# ProPrj_cdweather_2025-08-09.net
KiCad netlist of a schematic drawn in EasyEDA Pro
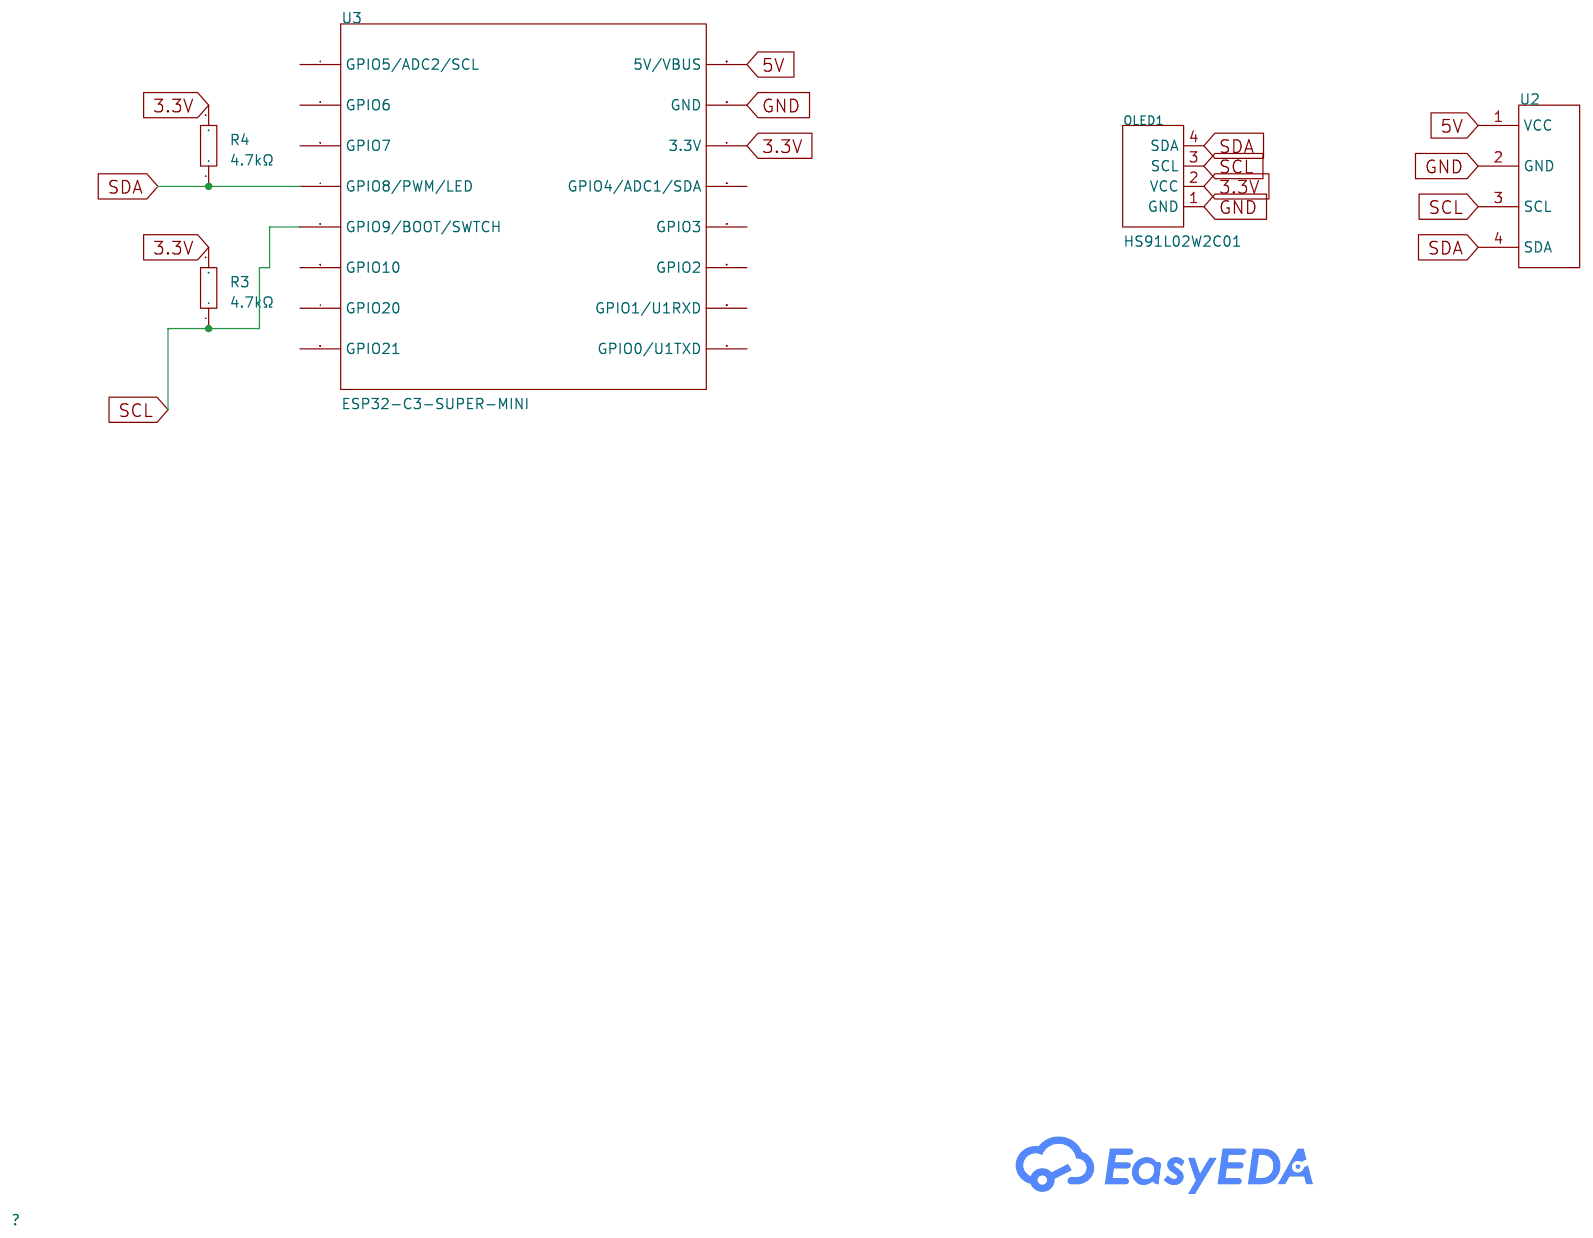
[diagram p0: schematic sheet]

(export (version "E")
  (design (tool "Eeschema 10.0.6"))
  (components
    (comp (ref "OLED1")
      (value "HS91L02W2C01")
      (footprint "easyedapro:OLED-TH_L38.0-W12.0_HS91L02W2C01")
      (fields (field (name "Manufacturer") "HS(汉昇)"))
      (libsource (lib "easyedapro") (part "HS91L02W2C01"))
    )
    (comp (ref "R3")
      (value "4.7kΩ")
      (footprint "easyedapro:RES-TH_BD2.3-L6.5-P10.50-D0.5")
      (fields
        (field (name "Manufacturer Part") "CF1/4W-4.7KΩ±5% T")
        (field (name "Manufacturer") "CCO(千志电子)")
      )
      (libsource (lib "easyedapro") (part "CF1/4W-4.7KΩ±5% T52"))
    )
    (comp (ref "R4")
      (value "4.7kΩ")
      (footprint "easyedapro:RES-TH_BD2.3-L6.5-P10.50-D0.5")
      (fields
        (field (name "Manufacturer Part") "CF1/4W-4.7KΩ±5% T")
        (field (name "Manufacturer") "CCO(千志电子)")
      )
      (libsource (lib "easyedapro") (part "CF1/4W-4.7KΩ±5% T52"))
    )
    (comp (ref "U2")
      (value "~")
      (footprint "easyedapro:BME280 Module - V")
      (libsource (lib "easyedapro") (part "BME280 Module - V"))
    )
    (comp (ref "U3")
      (value "ESP32-C3-SUPER-MINI")
      (fields (field (name "Manufacturer") "Maker go"))
      (libsource (lib "easyedapro") (part "ESP32-C3-SUPER-MINI"))
    )
  )
  (nets
    (net (code "1") (name "3.3V") (class "Default")
      (node (ref "OLED1") (pin "2") (pinfunction "VCC_2") (pintype "input"))
      (node (ref "R3") (pin "2") (pinfunction "2_2") (pintype "unspecified"))
      (node (ref "R4") (pin "2") (pinfunction "2_2") (pintype "unspecified"))
      (node (ref "U3") (pin "14") (pinfunction "3.3V_14") (pintype "unspecified"))
    )
    (net (code "2") (name "5V") (class "Default")
      (node (ref "U2") (pin "1") (pinfunction "VCC_1") (pintype "input"))
      (node (ref "U3") (pin "16") (pinfunction "5V/VBUS_16") (pintype "unspecified"))
    )
    (net (code "3") (name "GND") (class "Default")
      (node (ref "OLED1") (pin "1") (pinfunction "GND_1") (pintype "input"))
      (node (ref "U2") (pin "2") (pinfunction "GND_2") (pintype "input"))
      (node (ref "U3") (pin "15") (pinfunction "GND_15") (pintype "unspecified"))
    )
    (net (code "4") (name "SCL") (class "Default")
      (node (ref "OLED1") (pin "3") (pinfunction "SCL_3") (pintype "input"))
      (node (ref "R3") (pin "1") (pinfunction "1_1") (pintype "unspecified"))
      (node (ref "U2") (pin "3") (pinfunction "SCL_3") (pintype "input"))
      (node (ref "U3") (pin "5") (pinfunction "GPIO9/BOOT/SWTCH_5") (pintype "unspecified"))
    )
    (net (code "5") (name "SDA") (class "Default")
      (node (ref "OLED1") (pin "4") (pinfunction "SDA_4") (pintype "input"))
      (node (ref "R4") (pin "1") (pinfunction "1_1") (pintype "unspecified"))
      (node (ref "U2") (pin "4") (pinfunction "SDA_4") (pintype "input"))
      (node (ref "U3") (pin "4") (pinfunction "GPIO8/PWM/LED_4") (pintype "unspecified"))
    )
    (net (code "6") (name "unconnected-(U3-GPIO0{slash}U1TXD-Pad9)") (class "Default")
      (node (ref "U3") (pin "9") (pinfunction "GPIO0/U1TXD_9") (pintype "unspecified"))
    )
    (net (code "7") (name "unconnected-(U3-GPIO1{slash}U1RXD-Pad10)") (class "Default")
      (node (ref "U3") (pin "10") (pinfunction "GPIO1/U1RXD_10") (pintype "unspecified"))
    )
    (net (code "8") (name "unconnected-(U3-GPIO2-Pad11)") (class "Default")
      (node (ref "U3") (pin "11") (pinfunction "GPIO2_11") (pintype "unspecified"))
    )
    (net (code "9") (name "unconnected-(U3-GPIO3-Pad12)") (class "Default")
      (node (ref "U3") (pin "12") (pinfunction "GPIO3_12") (pintype "unspecified"))
    )
    (net (code "10") (name "unconnected-(U3-GPIO4{slash}ADC1{slash}SDA-Pad13)") (class "Default")
      (node (ref "U3") (pin "13") (pinfunction "GPIO4/ADC1/SDA_13") (pintype "unspecified"))
    )
    (net (code "11") (name "unconnected-(U3-GPIO5{slash}ADC2{slash}SCL-Pad1)") (class "Default")
      (node (ref "U3") (pin "1") (pinfunction "GPIO5/ADC2/SCL_1") (pintype "unspecified"))
    )
    (net (code "12") (name "unconnected-(U3-GPIO6-Pad2)") (class "Default")
      (node (ref "U3") (pin "2") (pinfunction "GPIO6_2") (pintype "unspecified"))
    )
    (net (code "13") (name "unconnected-(U3-GPIO7-Pad3)") (class "Default")
      (node (ref "U3") (pin "3") (pinfunction "GPIO7_3") (pintype "unspecified"))
    )
    (net (code "14") (name "unconnected-(U3-GPIO10-Pad6)") (class "Default")
      (node (ref "U3") (pin "6") (pinfunction "GPIO10_6") (pintype "unspecified"))
    )
    (net (code "15") (name "unconnected-(U3-GPIO20-Pad7)") (class "Default")
      (node (ref "U3") (pin "7") (pinfunction "GPIO20_7") (pintype "unspecified"))
    )
    (net (code "16") (name "unconnected-(U3-GPIO21-Pad8)") (class "Default")
      (node (ref "U3") (pin "8") (pinfunction "GPIO21_8") (pintype "unspecified"))
    )
  )
)
